# MCU_board_ATmega328p_v2_1.net
KiCad netlist of a schematic drawn in EAGLE
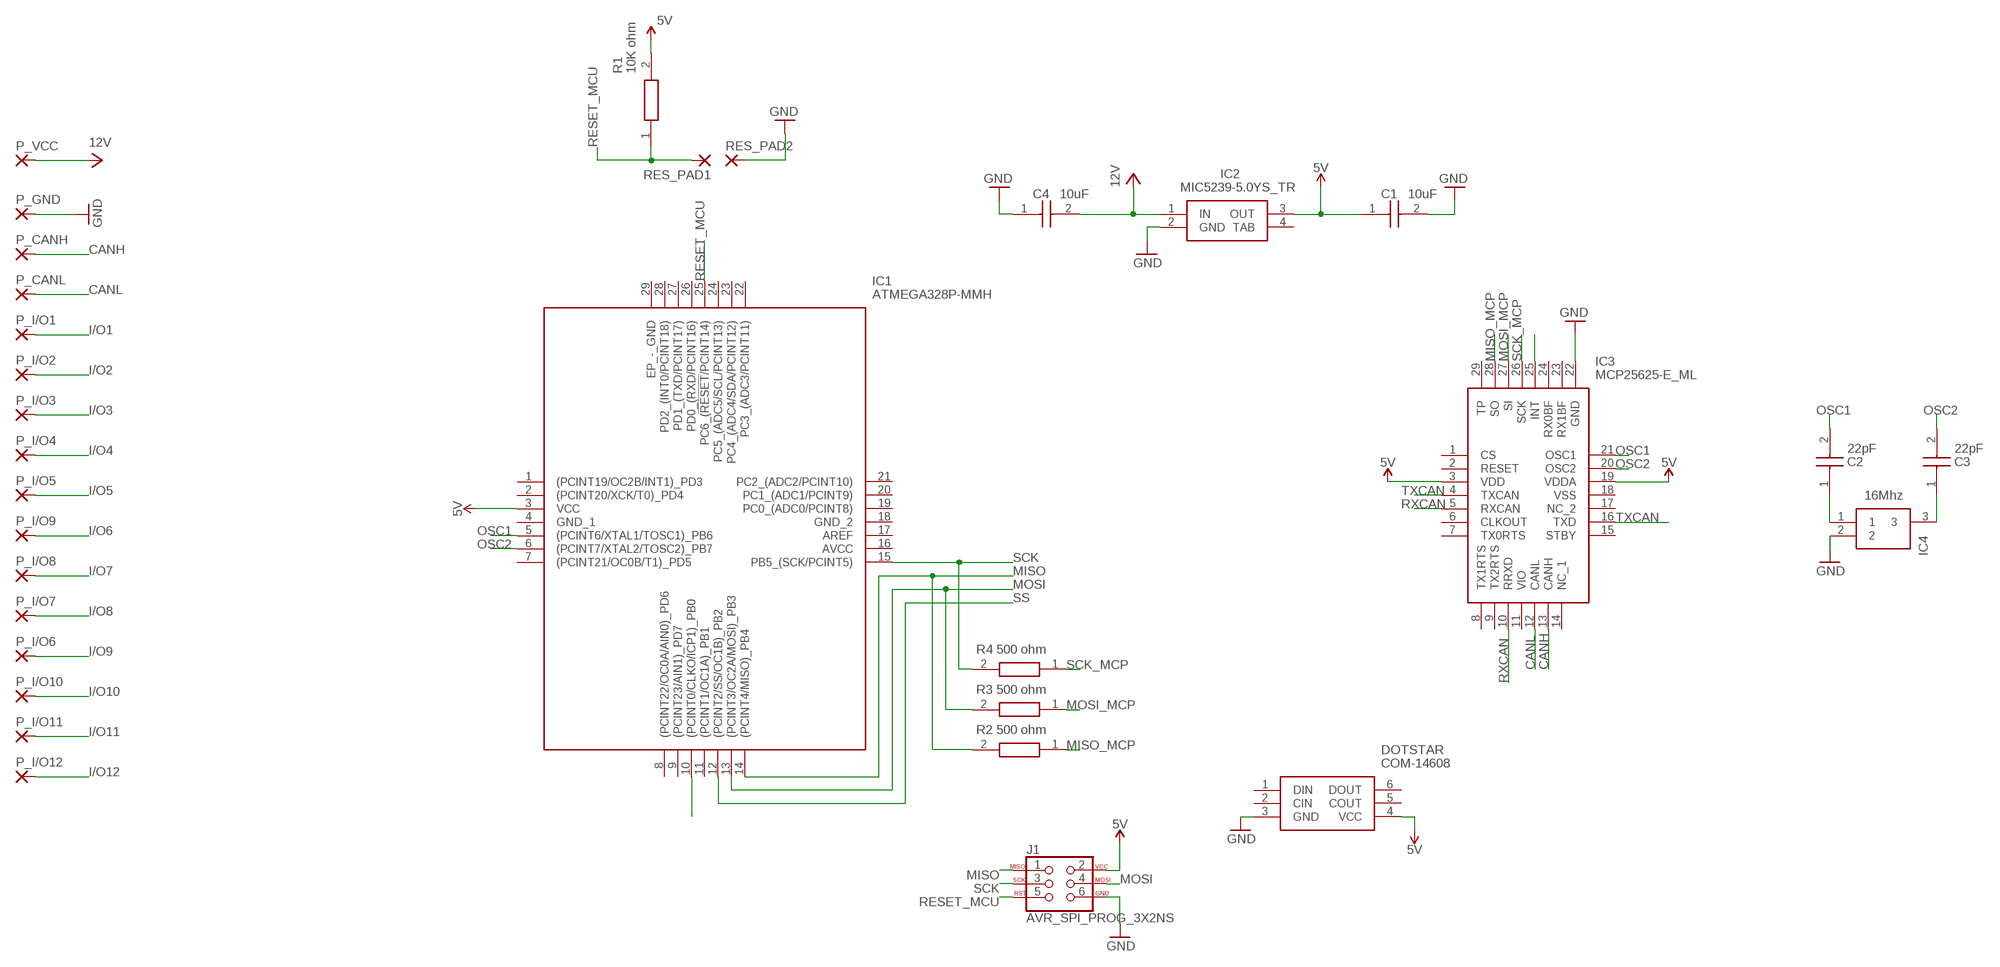
[diagram p0: schematic, sheet 1]

(export (version "E")
  (design (tool "Eeschema 10.0.6"))
  (components
    (comp (ref "C1")
      (value "10uF")
      (footprint "eagle-import:CAPPM3216X180N")
      (fields (field (name "ARROW_PART_NUMBER") "T491A106K016AT") (field (name "RS_PART_NUMBER") "1696687"))
      (libsource (lib "eagle-import") (part "T491A106K016AT"))
    )
    (comp (ref "C2")
      (value "22pF")
      (footprint "eagle-import:CAPC3216X229N")
      (fields (field (name "ARROW_PART_NUMBER") "12066D106KAT2A") (field (name "RS_PART_NUMBER") "1356756"))
      (libsource (lib "eagle-import") (part "12066D106KAT2A"))
    )
    (comp (ref "C3")
      (value "22pF")
      (footprint "eagle-import:CAPC3216X229N")
      (fields (field (name "ARROW_PART_NUMBER") "12066D106KAT2A") (field (name "RS_PART_NUMBER") "1356756"))
      (libsource (lib "eagle-import") (part "12066D106KAT2A"))
    )
    (comp (ref "C4")
      (value "10uF")
      (footprint "eagle-import:CAPPM3216X180N")
      (fields (field (name "ARROW_PART_NUMBER") "T491A106K016AT") (field (name "RS_PART_NUMBER") "1696687"))
      (libsource (lib "eagle-import") (part "T491A106K016AT"))
    )
    (comp (ref "DOTSTAR")
      (value "COM-14608")
      (footprint "eagle-import:SON75P200X200X100-6N")
      (libsource (lib "eagle-import") (part "COM-14608"))
    )
    (comp (ref "IC1")
      (value "ATMEGA328P-MMH")
      (footprint "eagle-import:QFN45P400X400X100-29N")
      (fields (field (name "RS_PART_NUMBER") "1310272P"))
      (libsource (lib "eagle-import") (part "ATMEGA328P-MMH"))
    )
    (comp (ref "IC2")
      (value "MIC5239-5.0YS_TR")
      (footprint "eagle-import:SOT230P700X170-4N")
      (fields
        (field (name "ARROW_PART_NUMBER") "MIC5239-5.0YS TR")
        (field (name "RS_PART_NUMBER") "7275535P")
      )
      (libsource (lib "eagle-import") (part "MIC5239-5.0YS_TR"))
    )
    (comp (ref "IC3")
      (value "MCP25625-E_ML")
      (footprint "eagle-import:QFN65P600X600X100-29N")
      (fields (field (name "ARROW_PART_NUMBER") "MCP25625-E/ML") (field (name "RS_PART_NUMBER") "1654104"))
      (libsource (lib "eagle-import") (part "MCP25625-E_ML"))
    )
    (comp (ref "IC4")
      (value "16Mhz")
      (footprint "eagle-import:CSTCE16M0V13C99R0")
      (fields
        (field (name "ARROW_PART_NUMBER") "CSTCE16M0V13C99-R0")
        (field (name "RS_PART_NUMBER") "1669513")
      )
      (libsource (lib "eagle-import") (part "CSTCE16M0V13C99-R0"))
    )
    (comp (ref "J1")
      (value "AVR_SPI_PROG_3X2NS")
      (footprint "eagle-import:2X3-NS")
      (libsource (lib "eagle-import") (part "AVR_SPI_PROG_3X2NS"))
    )
    (comp (ref "P_CANH")
      (value "2,15/1,0")
      (footprint "eagle-import:2,15_1,0")
      (libsource (lib "eagle-import") (part "2,15/1,0"))
    )
    (comp (ref "P_CANL")
      (value "2,15/1,0")
      (footprint "eagle-import:2,15_1,0")
      (libsource (lib "eagle-import") (part "2,15/1,0"))
    )
    (comp (ref "P_GND")
      (value "2,15/1,0")
      (footprint "eagle-import:2,15_1,0")
      (libsource (lib "eagle-import") (part "2,15/1,0"))
    )
    (comp (ref "P_I/O1")
      (value "2,15/1,0")
      (footprint "eagle-import:2,15_1,0")
      (libsource (lib "eagle-import") (part "2,15/1,0"))
    )
    (comp (ref "P_I/O2")
      (value "2,15/1,0")
      (footprint "eagle-import:2,15_1,0")
      (libsource (lib "eagle-import") (part "2,15/1,0"))
    )
    (comp (ref "P_I/O3")
      (value "2,15/1,0")
      (footprint "eagle-import:2,15_1,0")
      (libsource (lib "eagle-import") (part "2,15/1,0"))
    )
    (comp (ref "P_I/O4")
      (value "2,15/1,0")
      (footprint "eagle-import:2,15_1,0")
      (libsource (lib "eagle-import") (part "2,15/1,0"))
    )
    (comp (ref "P_I/O5")
      (value "2,15/1,0")
      (footprint "eagle-import:2,15_1,0")
      (libsource (lib "eagle-import") (part "2,15/1,0"))
    )
    (comp (ref "P_I/O6")
      (value "2,15/1,0")
      (footprint "eagle-import:2,15_1,0")
      (libsource (lib "eagle-import") (part "2,15/1,0"))
    )
    (comp (ref "P_I/O7")
      (value "2,15/1,0")
      (footprint "eagle-import:2,15_1,0")
      (libsource (lib "eagle-import") (part "2,15/1,0"))
    )
    (comp (ref "P_I/O8")
      (value "2,15/1,0")
      (footprint "eagle-import:2,15_1,0")
      (libsource (lib "eagle-import") (part "2,15/1,0"))
    )
    (comp (ref "P_I/O9")
      (value "2,15/1,0")
      (footprint "eagle-import:2,15_1,0")
      (libsource (lib "eagle-import") (part "2,15/1,0"))
    )
    (comp (ref "P_I/O10")
      (value "2,15/1,0")
      (footprint "eagle-import:2,15_1,0")
      (libsource (lib "eagle-import") (part "2,15/1,0"))
    )
    (comp (ref "P_I/O11")
      (value "2,15/1,0")
      (footprint "eagle-import:2,15_1,0")
      (libsource (lib "eagle-import") (part "2,15/1,0"))
    )
    (comp (ref "P_I/O12")
      (value "2,15/1,0")
      (footprint "eagle-import:2,15_1,0")
      (libsource (lib "eagle-import") (part "2,15/1,0"))
    )
    (comp (ref "P_VCC")
      (value "2,15/1,0")
      (footprint "eagle-import:2,15_1,0")
      (libsource (lib "eagle-import") (part "2,15/1,0"))
    )
    (comp (ref "R1")
      (value "10K ohm")
      (footprint "eagle-import:RESC0603X28N")
      (fields (field (name "ARROW_PART_NUMBER") "CPF0201D10KC1") (field (name "RS_PART_NUMBER") "7549833"))
      (libsource (lib "eagle-import") (part "CPF0201D10KC1"))
    )
    (comp (ref "R2")
      (value "500 ohm")
      (footprint "eagle-import:RESC0603X28N")
      (fields (field (name "ARROW_PART_NUMBER") "CPF0201D10KC1") (field (name "RS_PART_NUMBER") "7549833"))
      (libsource (lib "eagle-import") (part "CPF0201D10KC1"))
    )
    (comp (ref "R3")
      (value "500 ohm")
      (footprint "eagle-import:RESC0603X28N")
      (fields (field (name "ARROW_PART_NUMBER") "CPF0201D10KC1") (field (name "RS_PART_NUMBER") "7549833"))
      (libsource (lib "eagle-import") (part "CPF0201D10KC1"))
    )
    (comp (ref "R4")
      (value "500 ohm")
      (footprint "eagle-import:RESC0603X28N")
      (fields (field (name "ARROW_PART_NUMBER") "CPF0201D10KC1") (field (name "RS_PART_NUMBER") "7549833"))
      (libsource (lib "eagle-import") (part "CPF0201D10KC1"))
    )
    (comp (ref "RES_PAD1")
      (value "SMD2")
      (footprint "eagle-import:SMD1,27-2,54")
      (libsource (lib "eagle-import") (part "SMD2"))
    )
    (comp (ref "RES_PAD2")
      (value "SMD2")
      (footprint "eagle-import:SMD1,27-2,54")
      (libsource (lib "eagle-import") (part "SMD2"))
    )
  )
  (nets
    (net (code "1") (name "/CANH") (class "Default")
      (node (ref "IC3") (pin "13") (pinfunction "CANH_13") (pintype "bidirectional"))
      (node (ref "P_CANH") (pin "1") (pinfunction "P_1") (pintype "passive"))
    )
    (net (code "2") (name "/CANL") (class "Default")
      (node (ref "IC3") (pin "12") (pinfunction "CANL_12") (pintype "bidirectional"))
      (node (ref "P_CANL") (pin "1") (pinfunction "P_1") (pintype "passive"))
    )
    (net (code "3") (name "/I{slash}O1") (class "Default")
      (node (ref "P_I/O1") (pin "1") (pinfunction "P_1") (pintype "passive"))
    )
    (net (code "4") (name "/I{slash}O2") (class "Default")
      (node (ref "P_I/O2") (pin "1") (pinfunction "P_1") (pintype "passive"))
    )
    (net (code "5") (name "/I{slash}O3") (class "Default")
      (node (ref "P_I/O3") (pin "1") (pinfunction "P_1") (pintype "passive"))
    )
    (net (code "6") (name "/I{slash}O4") (class "Default")
      (node (ref "P_I/O4") (pin "1") (pinfunction "P_1") (pintype "passive"))
    )
    (net (code "7") (name "/I{slash}O5") (class "Default")
      (node (ref "P_I/O5") (pin "1") (pinfunction "P_1") (pintype "passive"))
    )
    (net (code "8") (name "/I{slash}O6") (class "Default")
      (node (ref "P_I/O9") (pin "1") (pinfunction "P_1") (pintype "passive"))
    )
    (net (code "9") (name "/I{slash}O7") (class "Default")
      (node (ref "P_I/O8") (pin "1") (pinfunction "P_1") (pintype "passive"))
    )
    (net (code "10") (name "/I{slash}O8") (class "Default")
      (node (ref "P_I/O7") (pin "1") (pinfunction "P_1") (pintype "passive"))
    )
    (net (code "11") (name "/I{slash}O9") (class "Default")
      (node (ref "P_I/O6") (pin "1") (pinfunction "P_1") (pintype "passive"))
    )
    (net (code "12") (name "/I{slash}O10") (class "Default")
      (node (ref "P_I/O10") (pin "1") (pinfunction "P_1") (pintype "passive"))
    )
    (net (code "13") (name "/I{slash}O11") (class "Default")
      (node (ref "P_I/O11") (pin "1") (pinfunction "P_1") (pintype "passive"))
    )
    (net (code "14") (name "/I{slash}O12") (class "Default")
      (node (ref "P_I/O12") (pin "1") (pinfunction "P_1") (pintype "passive"))
    )
    (net (code "15") (name "/MISO") (class "Default")
      (node (ref "IC1") (pin "14") (pinfunction "(PCINT4/MISO)_PB4_14") (pintype "bidirectional"))
      (node (ref "J1") (pin "1") (pinfunction "1_1") (pintype "passive"))
      (node (ref "R2") (pin "2") (pinfunction "2_2") (pintype "bidirectional"))
    )
    (net (code "16") (name "/MISO_MCP") (class "Default")
      (node (ref "IC3") (pin "28") (pinfunction "SO_28") (pintype "bidirectional"))
      (node (ref "R2") (pin "1") (pinfunction "1_1") (pintype "bidirectional"))
    )
    (net (code "17") (name "/MOSI") (class "Default")
      (node (ref "IC1") (pin "13") (pinfunction "(PCINT3/OC2A/MOSI)_PB3_13") (pintype "bidirectional"))
      (node (ref "J1") (pin "4") (pinfunction "4_4") (pintype "passive"))
      (node (ref "R3") (pin "2") (pinfunction "2_2") (pintype "bidirectional"))
    )
    (net (code "18") (name "/MOSI_MCP") (class "Default")
      (node (ref "IC3") (pin "27") (pinfunction "SI_27") (pintype "bidirectional"))
      (node (ref "R3") (pin "1") (pinfunction "1_1") (pintype "bidirectional"))
    )
    (net (code "19") (name "/OSC1") (class "Default")
      (node (ref "C2") (pin "2") (pinfunction "2_2") (pintype "bidirectional"))
      (node (ref "IC1") (pin "5") (pinfunction "(PCINT6/XTAL1/TOSC1)_PB6_5") (pintype "bidirectional"))
      (node (ref "IC3") (pin "21") (pinfunction "OSC1_21") (pintype "bidirectional"))
    )
    (net (code "20") (name "/OSC2") (class "Default")
      (node (ref "C3") (pin "2") (pinfunction "2_2") (pintype "bidirectional"))
      (node (ref "IC1") (pin "6") (pinfunction "(PCINT7/XTAL2/TOSC2)_PB7_6") (pintype "bidirectional"))
      (node (ref "IC3") (pin "20") (pinfunction "OSC2_20") (pintype "bidirectional"))
    )
    (net (code "21") (name "/RESET_MCU") (class "Default")
      (node (ref "IC1") (pin "25") (pinfunction "PC6_(~{RESET}/PCINT14)_25") (pintype "bidirectional"))
      (node (ref "J1") (pin "5") (pinfunction "5_5") (pintype "passive"))
      (node (ref "R1") (pin "1") (pinfunction "1_1") (pintype "bidirectional"))
      (node (ref "RES_PAD1") (pin "1") (pinfunction "P_1") (pintype "passive"))
    )
    (net (code "22") (name "/RXCAN") (class "Default")
      (node (ref "IC3") (pin "10") (pinfunction "RRXD_10") (pintype "bidirectional"))
      (node (ref "IC3") (pin "5") (pinfunction "RXCAN_5") (pintype "bidirectional"))
    )
    (net (code "23") (name "/SCK") (class "Default")
      (node (ref "IC1") (pin "15") (pinfunction "PB5_(SCK/PCINT5)_15") (pintype "bidirectional"))
      (node (ref "J1") (pin "3") (pinfunction "3_3") (pintype "passive"))
      (node (ref "R4") (pin "2") (pinfunction "2_2") (pintype "bidirectional"))
    )
    (net (code "24") (name "/SCK_MCP") (class "Default")
      (node (ref "IC3") (pin "26") (pinfunction "SCK_26") (pintype "bidirectional"))
      (node (ref "R4") (pin "1") (pinfunction "1_1") (pintype "bidirectional"))
    )
    (net (code "25") (name "/SS") (class "Default")
      (node (ref "IC1") (pin "12") (pinfunction "(PCINT2/SS/OC1B)_PB2_12") (pintype "bidirectional"))
    )
    (net (code "26") (name "/TXCAN") (class "Default")
      (node (ref "IC3") (pin "16") (pinfunction "TXD_16") (pintype "bidirectional"))
      (node (ref "IC3") (pin "4") (pinfunction "TXCAN_4") (pintype "bidirectional"))
    )
    (net (code "27") (name "/VSS") (class "Default")
      (node (ref "IC3") (pin "18") (pinfunction "VSS_18") (pintype "power_in"))
    )
    (net (code "28") (name "5V") (class "Default")
      (node (ref "C1") (pin "1") (pinfunction "K_1") (pintype "bidirectional"))
      (node (ref "DOTSTAR") (pin "4") (pinfunction "VCC_4") (pintype "bidirectional"))
      (node (ref "IC1") (pin "3") (pinfunction "VCC_3") (pintype "bidirectional"))
      (node (ref "IC2") (pin "3") (pinfunction "OUT_3") (pintype "bidirectional"))
      (node (ref "IC3") (pin "19") (pinfunction "VDDA_19") (pintype "power_in"))
      (node (ref "IC3") (pin "3") (pinfunction "VDD_3") (pintype "power_in"))
      (node (ref "J1") (pin "2") (pinfunction "2_2") (pintype "passive"))
      (node (ref "R1") (pin "2") (pinfunction "2_2") (pintype "bidirectional"))
    )
    (net (code "29") (name "12V") (class "Default")
      (node (ref "C4") (pin "2") (pinfunction "A_2") (pintype "bidirectional"))
      (node (ref "IC2") (pin "1") (pinfunction "IN_1") (pintype "bidirectional"))
      (node (ref "P_VCC") (pin "1") (pinfunction "P_1") (pintype "passive"))
    )
    (net (code "30") (name "GND") (class "Default")
      (node (ref "C1") (pin "2") (pinfunction "A_2") (pintype "bidirectional"))
      (node (ref "C4") (pin "1") (pinfunction "K_1") (pintype "bidirectional"))
      (node (ref "DOTSTAR") (pin "3") (pinfunction "GND_3") (pintype "bidirectional"))
      (node (ref "IC2") (pin "2") (pinfunction "GND_2") (pintype "bidirectional"))
      (node (ref "IC3") (pin "22") (pinfunction "GND_22") (pintype "power_in"))
      (node (ref "IC4") (pin "2") (pinfunction "2_2") (pintype "bidirectional"))
      (node (ref "J1") (pin "6") (pinfunction "6_6") (pintype "passive"))
      (node (ref "P_GND") (pin "1") (pinfunction "P_1") (pintype "passive"))
      (node (ref "RES_PAD2") (pin "1") (pinfunction "P_1") (pintype "passive"))
    )
    (net (code "31") (name "Net-(C2-Pad1)") (class "Default")
      (node (ref "C2") (pin "1") (pinfunction "1_1") (pintype "bidirectional"))
      (node (ref "IC4") (pin "1") (pinfunction "1_1") (pintype "bidirectional"))
    )
    (net (code "32") (name "Net-(C3-Pad1)") (class "Default")
      (node (ref "C3") (pin "1") (pinfunction "1_1") (pintype "bidirectional"))
      (node (ref "IC4") (pin "3") (pinfunction "3_3") (pintype "bidirectional"))
    )
    (net (code "33") (name "unconnected-(DOTSTAR-CIN-Pad2)") (class "Default")
      (node (ref "DOTSTAR") (pin "2") (pinfunction "CIN_2") (pintype "bidirectional"))
    )
    (net (code "34") (name "unconnected-(DOTSTAR-COUT-Pad5)") (class "Default")
      (node (ref "DOTSTAR") (pin "5") (pinfunction "COUT_5") (pintype "bidirectional"))
    )
    (net (code "35") (name "unconnected-(DOTSTAR-DIN-Pad1)") (class "Default")
      (node (ref "DOTSTAR") (pin "1") (pinfunction "DIN_1") (pintype "bidirectional"))
    )
    (net (code "36") (name "unconnected-(DOTSTAR-DOUT-Pad6)") (class "Default")
      (node (ref "DOTSTAR") (pin "6") (pinfunction "DOUT_6") (pintype "bidirectional"))
    )
    (net (code "37") (name "unconnected-(IC1-(PCINT0{slash}CLKO{slash}ICP1)_PB0-Pad10)") (class "Default")
      (node (ref "IC1") (pin "10") (pinfunction "(PCINT0/CLKO/ICP1)_PB0_10") (pintype "bidirectional"))
    )
    (net (code "38") (name "unconnected-(IC1-(PCINT1{slash}OC1A)_PB1-Pad11)") (class "Default")
      (node (ref "IC1") (pin "11") (pinfunction "(PCINT1/OC1A)_PB1_11") (pintype "bidirectional"))
    )
    (net (code "39") (name "unconnected-(IC1-(PCINT19{slash}OC2B{slash}INT1)_PD3-Pad1)") (class "Default")
      (node (ref "IC1") (pin "1") (pinfunction "(PCINT19/OC2B/INT1)_PD3_1") (pintype "bidirectional"))
    )
    (net (code "40") (name "unconnected-(IC1-(PCINT20{slash}XCK{slash}T0)_PD4-Pad2)") (class "Default")
      (node (ref "IC1") (pin "2") (pinfunction "(PCINT20/XCK/T0)_PD4_2") (pintype "bidirectional"))
    )
    (net (code "41") (name "unconnected-(IC1-(PCINT21{slash}OC0B{slash}T1)_PD5-Pad7)") (class "Default")
      (node (ref "IC1") (pin "7") (pinfunction "(PCINT21/OC0B/T1)_PD5_7") (pintype "bidirectional"))
    )
    (net (code "42") (name "unconnected-(IC1-(PCINT22{slash}OC0A{slash}AIN0)_PD6-Pad8)") (class "Default")
      (node (ref "IC1") (pin "8") (pinfunction "(PCINT22/OC0A/AIN0)_PD6_8") (pintype "bidirectional"))
    )
    (net (code "43") (name "unconnected-(IC1-(PCINT23{slash}AIN1)_PD7-Pad9)") (class "Default")
      (node (ref "IC1") (pin "9") (pinfunction "(PCINT23/AIN1)_PD7_9") (pintype "bidirectional"))
    )
    (net (code "44") (name "unconnected-(IC1-AREF-Pad17)") (class "Default")
      (node (ref "IC1") (pin "17") (pinfunction "AREF_17") (pintype "bidirectional"))
    )
    (net (code "45") (name "unconnected-(IC1-AVCC-Pad16)") (class "Default")
      (node (ref "IC1") (pin "16") (pinfunction "AVCC_16") (pintype "bidirectional"))
    )
    (net (code "46") (name "unconnected-(IC1-EP_-_GND-Pad29)") (class "Default")
      (node (ref "IC1") (pin "29") (pinfunction "EP_-_GND_29") (pintype "bidirectional"))
    )
    (net (code "47") (name "unconnected-(IC1-GND_1-Pad4)") (class "Default")
      (node (ref "IC1") (pin "4") (pinfunction "GND_1_4") (pintype "bidirectional"))
    )
    (net (code "48") (name "unconnected-(IC1-GND_2-Pad18)") (class "Default")
      (node (ref "IC1") (pin "18") (pinfunction "GND_2_18") (pintype "bidirectional"))
    )
    (net (code "49") (name "unconnected-(IC1-PC0_(ADC0{slash}PCINT8)-Pad19)") (class "Default")
      (node (ref "IC1") (pin "19") (pinfunction "PC0_(ADC0/PCINT8)_19") (pintype "bidirectional"))
    )
    (net (code "50") (name "unconnected-(IC1-PC1_(ADC1{slash}PCINT9)-Pad20)") (class "Default")
      (node (ref "IC1") (pin "20") (pinfunction "PC1_(ADC1/PCINT9)_20") (pintype "bidirectional"))
    )
    (net (code "51") (name "unconnected-(IC1-PC2_(ADC2{slash}PCINT10)-Pad21)") (class "Default")
      (node (ref "IC1") (pin "21") (pinfunction "PC2_(ADC2/PCINT10)_21") (pintype "bidirectional"))
    )
    (net (code "52") (name "unconnected-(IC1-PC3_(ADC3{slash}PCINT11)-Pad22)") (class "Default")
      (node (ref "IC1") (pin "22") (pinfunction "PC3_(ADC3/PCINT11)_22") (pintype "bidirectional"))
    )
    (net (code "53") (name "unconnected-(IC1-PC4_(ADC4{slash}SDA{slash}PCINT12)-Pad23)") (class "Default")
      (node (ref "IC1") (pin "23") (pinfunction "PC4_(ADC4/SDA/PCINT12)_23") (pintype "bidirectional"))
    )
    (net (code "54") (name "unconnected-(IC1-PC5_(ADC5{slash}SCL{slash}PCINT13)-Pad24)") (class "Default")
      (node (ref "IC1") (pin "24") (pinfunction "PC5_(ADC5/SCL/PCINT13)_24") (pintype "bidirectional"))
    )
    (net (code "55") (name "unconnected-(IC1-PD0_(RXD{slash}PCINT16)-Pad26)") (class "Default")
      (node (ref "IC1") (pin "26") (pinfunction "PD0_(RXD/PCINT16)_26") (pintype "bidirectional"))
    )
    (net (code "56") (name "unconnected-(IC1-PD1_(TXD{slash}PCINT17)-Pad27)") (class "Default")
      (node (ref "IC1") (pin "27") (pinfunction "PD1_(TXD/PCINT17)_27") (pintype "bidirectional"))
    )
    (net (code "57") (name "unconnected-(IC1-PD2_(INT0{slash}PCINT18)-Pad28)") (class "Default")
      (node (ref "IC1") (pin "28") (pinfunction "PD2_(INT0/PCINT18)_28") (pintype "bidirectional"))
    )
    (net (code "58") (name "unconnected-(IC2-TAB-Pad4)") (class "Default")
      (node (ref "IC2") (pin "4") (pinfunction "TAB_4") (pintype "bidirectional"))
    )
    (net (code "59") (name "unconnected-(IC3-CLKOUT-Pad6)") (class "Default")
      (node (ref "IC3") (pin "6") (pinfunction "CLKOUT_6") (pintype "output"))
    )
    (net (code "60") (name "unconnected-(IC3-CS-Pad1)") (class "Default")
      (node (ref "IC3") (pin "1") (pinfunction "CS_1") (pintype "input"))
    )
    (net (code "61") (name "unconnected-(IC3-INT-Pad25)") (class "Default")
      (node (ref "IC3") (pin "25") (pinfunction "INT_25") (pintype "input"))
    )
    (net (code "62") (name "unconnected-(IC3-NC_1-Pad14)") (class "Default")
      (node (ref "IC3") (pin "14") (pinfunction "NC_1_14") (pintype "bidirectional"))
    )
    (net (code "63") (name "unconnected-(IC3-NC_2-Pad17)") (class "Default")
      (node (ref "IC3") (pin "17") (pinfunction "NC_2_17") (pintype "bidirectional"))
    )
    (net (code "64") (name "unconnected-(IC3-RESET-Pad2)") (class "Default")
      (node (ref "IC3") (pin "2") (pinfunction "RESET_2") (pintype "bidirectional"))
    )
    (net (code "65") (name "unconnected-(IC3-RX0BF-Pad24)") (class "Default")
      (node (ref "IC3") (pin "24") (pinfunction "RX0BF_24") (pintype "bidirectional"))
    )
    (net (code "66") (name "unconnected-(IC3-RX1BF-Pad23)") (class "Default")
      (node (ref "IC3") (pin "23") (pinfunction "RX1BF_23") (pintype "bidirectional"))
    )
    (net (code "67") (name "unconnected-(IC3-STBY-Pad15)") (class "Default")
      (node (ref "IC3") (pin "15") (pinfunction "STBY_15") (pintype "bidirectional"))
    )
    (net (code "68") (name "unconnected-(IC3-TP-Pad29)") (class "Default")
      (node (ref "IC3") (pin "29") (pinfunction "TP_29") (pintype "bidirectional"))
    )
    (net (code "69") (name "unconnected-(IC3-TX0RTS-Pad7)") (class "Default")
      (node (ref "IC3") (pin "7") (pinfunction "TX0RTS_7") (pintype "bidirectional"))
    )
    (net (code "70") (name "unconnected-(IC3-TX1RTS-Pad8)") (class "Default")
      (node (ref "IC3") (pin "8") (pinfunction "TX1RTS_8") (pintype "bidirectional"))
    )
    (net (code "71") (name "unconnected-(IC3-TX2RTS-Pad9)") (class "Default")
      (node (ref "IC3") (pin "9") (pinfunction "TX2RTS_9") (pintype "bidirectional"))
    )
    (net (code "72") (name "unconnected-(IC3-VIO-Pad11)") (class "Default")
      (node (ref "IC3") (pin "11") (pinfunction "VIO_11") (pintype "bidirectional"))
    )
  )
)
